# RPI_v5_PCM5122brd.net
KiCad netlist of a schematic drawn in EAGLE
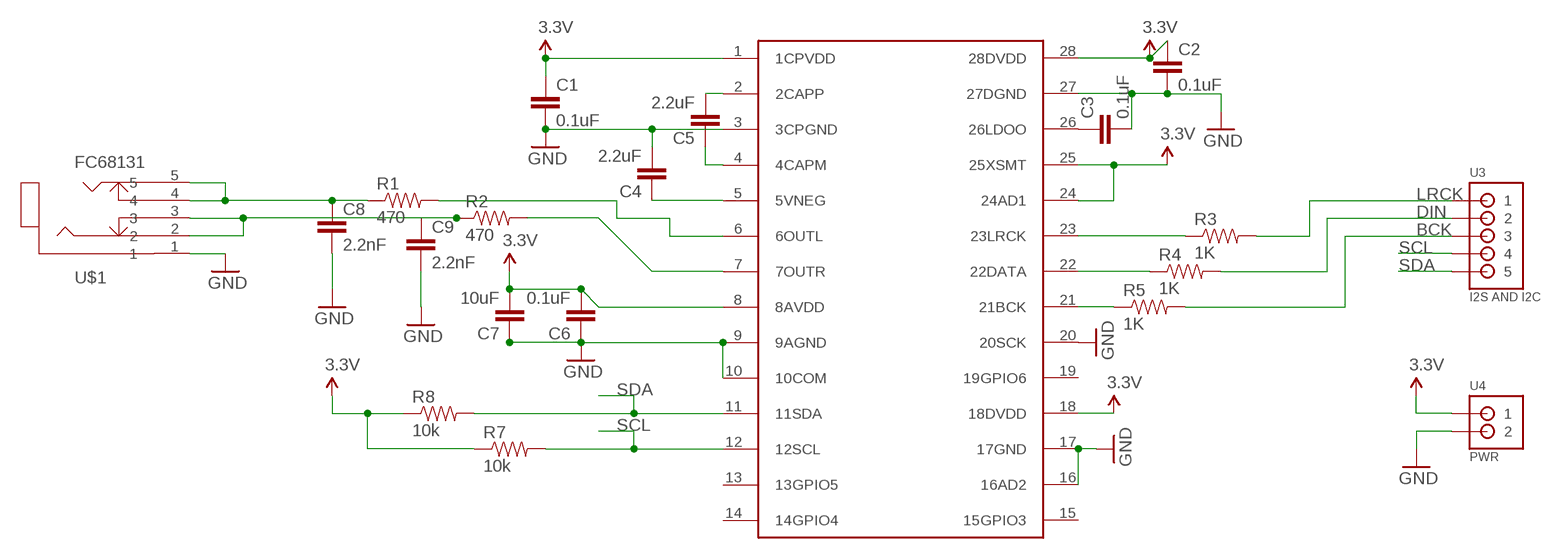
[diagram p0: schematic, sheet 1]

(export (version "E")
  (design (tool "Eeschema 10.0.6"))
  (components
    (comp (ref "C1")
      (value "0.1uF")
      (footprint "eagle-import:0805")
      (libsource (lib "eagle-import") (part "CAP0805"))
    )
    (comp (ref "C2")
      (value "0.1uF")
      (footprint "eagle-import:0805")
      (libsource (lib "eagle-import") (part "CAP0805"))
    )
    (comp (ref "C3")
      (value "0.1uF")
      (footprint "eagle-import:0805")
      (libsource (lib "eagle-import") (part "CAP0805"))
    )
    (comp (ref "C4")
      (value "2.2uF")
      (footprint "eagle-import:0805")
      (libsource (lib "eagle-import") (part "CAP0805"))
    )
    (comp (ref "C5")
      (value "2.2uF")
      (footprint "eagle-import:0805")
      (libsource (lib "eagle-import") (part "CAP0805"))
    )
    (comp (ref "C6")
      (value "0.1uF")
      (footprint "eagle-import:0805")
      (libsource (lib "eagle-import") (part "CAP0805"))
    )
    (comp (ref "C7")
      (value "10uF")
      (footprint "eagle-import:0805")
      (libsource (lib "eagle-import") (part "CAP0805"))
    )
    (comp (ref "C8")
      (value "2.2nF")
      (footprint "eagle-import:CAP-PTH-5MM")
      (libsource (lib "eagle-import") (part "CAPPTH1"))
    )
    (comp (ref "C9")
      (value "2.2nF")
      (footprint "eagle-import:CAP-PTH-5MM")
      (libsource (lib "eagle-import") (part "CAPPTH1"))
    )
    (comp (ref "R1")
      (value "470")
      (footprint "eagle-import:AXIAL-0.4")
      (libsource (lib "eagle-import") (part "RESISTORPTH-1/4W"))
    )
    (comp (ref "R2")
      (value "470")
      (footprint "eagle-import:AXIAL-0.4")
      (libsource (lib "eagle-import") (part "RESISTORPTH-1/4W"))
    )
    (comp (ref "R3")
      (value "1K")
      (footprint "eagle-import:0805")
      (libsource (lib "eagle-import") (part "RESISTOR0805-RES"))
    )
    (comp (ref "R4")
      (value "1K")
      (footprint "eagle-import:0805")
      (libsource (lib "eagle-import") (part "RESISTOR0805-RES"))
    )
    (comp (ref "R5")
      (value "1K")
      (footprint "eagle-import:0805")
      (libsource (lib "eagle-import") (part "RESISTOR0805-RES"))
    )
    (comp (ref "R7")
      (value "10k")
      (footprint "eagle-import:1206")
      (libsource (lib "eagle-import") (part "RESISTOR1206"))
    )
    (comp (ref "R8")
      (value "10k")
      (footprint "eagle-import:1206")
      (libsource (lib "eagle-import") (part "RESISTOR1206"))
    )
    (comp (ref "U$1")
      (value "FC68131")
      (footprint "eagle-import:FC68131-5P")
      (libsource (lib "eagle-import") (part "FC68131"))
    )
    (comp (ref "U$5")
      (value "PCM5122")
      (footprint "eagle-import:TSSOP28")
      (libsource (lib "eagle-import") (part "PCM5122"))
    )
    (comp (ref "U3")
      (value "I2S AND I2C")
      (footprint "eagle-import:JST_B5B-PH_HEADER")
      (libsource (lib "eagle-import") (part "JST-PH_5-PIN_HEADER"))
    )
    (comp (ref "U4")
      (value "PWR")
      (footprint "eagle-import:JST_B2B-PH_HEADER")
      (libsource (lib "eagle-import") (part "JST-PH_2-PIN_HEADER"))
    )
  )
  (nets
    (net (code "1") (name "/BCK") (class "Default")
      (node (ref "R5") (pin "2") (pinfunction "2_2") (pintype "passive"))
      (node (ref "U3") (pin "P3") (pinfunction "3_P3") (pintype "bidirectional"))
    )
    (net (code "2") (name "/DIN") (class "Default")
      (node (ref "R4") (pin "2") (pinfunction "2_2") (pintype "passive"))
      (node (ref "U3") (pin "P2") (pinfunction "2_P2") (pintype "bidirectional"))
    )
    (net (code "3") (name "/LRCK") (class "Default")
      (node (ref "R3") (pin "2") (pinfunction "2_2") (pintype "passive"))
      (node (ref "U3") (pin "P1") (pinfunction "1_P1") (pintype "bidirectional"))
    )
    (net (code "4") (name "/SCL") (class "Default")
      (node (ref "R7") (pin "2") (pinfunction "2_2") (pintype "passive"))
      (node (ref "U$5") (pin "12") (pinfunction "12SCL_12") (pintype "bidirectional"))
      (node (ref "U3") (pin "P4") (pinfunction "4_P4") (pintype "bidirectional"))
    )
    (net (code "5") (name "/SDA") (class "Default")
      (node (ref "R8") (pin "2") (pinfunction "2_2") (pintype "passive"))
      (node (ref "U$5") (pin "11") (pinfunction "11SDA_11") (pintype "bidirectional"))
      (node (ref "U3") (pin "P5") (pinfunction "5_P5") (pintype "bidirectional"))
    )
    (net (code "6") (name "3.3V") (class "Default")
      (node (ref "C1") (pin "1") (pinfunction "1_1") (pintype "passive"))
      (node (ref "C2") (pin "1") (pinfunction "1_1") (pintype "passive"))
      (node (ref "C6") (pin "2") (pinfunction "2_2") (pintype "passive"))
      (node (ref "C7") (pin "2") (pinfunction "2_2") (pintype "passive"))
      (node (ref "R7") (pin "1") (pinfunction "1_1") (pintype "passive"))
      (node (ref "R8") (pin "1") (pinfunction "1_1") (pintype "passive"))
      (node (ref "U$5") (pin "1") (pinfunction "1CPVDD_1") (pintype "bidirectional"))
      (node (ref "U$5") (pin "18") (pinfunction "18DVDD_18") (pintype "bidirectional"))
      (node (ref "U$5") (pin "24") (pinfunction "24AD1_24") (pintype "bidirectional"))
      (node (ref "U$5") (pin "25") (pinfunction "25XSMT_25") (pintype "bidirectional"))
      (node (ref "U$5") (pin "28") (pinfunction "28DVDD_28") (pintype "bidirectional"))
      (node (ref "U$5") (pin "8") (pinfunction "8AVDD_8") (pintype "bidirectional"))
      (node (ref "U4") (pin "P1") (pinfunction "1_P1") (pintype "bidirectional"))
    )
    (net (code "7") (name "GND") (class "Default")
      (node (ref "C1") (pin "2") (pinfunction "2_2") (pintype "passive"))
      (node (ref "C2") (pin "2") (pinfunction "2_2") (pintype "passive"))
      (node (ref "C3") (pin "2") (pinfunction "2_2") (pintype "passive"))
      (node (ref "C4") (pin "2") (pinfunction "2_2") (pintype "passive"))
      (node (ref "C6") (pin "1") (pinfunction "1_1") (pintype "passive"))
      (node (ref "C7") (pin "1") (pinfunction "1_1") (pintype "passive"))
      (node (ref "C8") (pin "2") (pinfunction "2_2") (pintype "passive"))
      (node (ref "C9") (pin "2") (pinfunction "2_2") (pintype "passive"))
      (node (ref "U$1") (pin "1") (pinfunction "1_1") (pintype "bidirectional"))
      (node (ref "U$5") (pin "10") (pinfunction "10COM_10") (pintype "bidirectional"))
      (node (ref "U$5") (pin "16") (pinfunction "16AD2_16") (pintype "bidirectional"))
      (node (ref "U$5") (pin "17") (pinfunction "17GND_17") (pintype "bidirectional"))
      (node (ref "U$5") (pin "20") (pinfunction "20SCK_20") (pintype "bidirectional"))
      (node (ref "U$5") (pin "27") (pinfunction "27DGND_27") (pintype "bidirectional"))
      (node (ref "U$5") (pin "3") (pinfunction "3CPGND_3") (pintype "bidirectional"))
      (node (ref "U$5") (pin "9") (pinfunction "9AGND_9") (pintype "bidirectional"))
      (node (ref "U4") (pin "P2") (pinfunction "2_P2") (pintype "bidirectional"))
    )
    (net (code "8") (name "Net-(R1-1)") (class "Default")
      (node (ref "C8") (pin "1") (pinfunction "1_1") (pintype "passive"))
      (node (ref "R1") (pin "P$1") (pinfunction "1_P$1") (pintype "passive"))
      (node (ref "U$1") (pin "4") (pinfunction "4_4") (pintype "bidirectional"))
      (node (ref "U$1") (pin "5") (pinfunction "5_5") (pintype "bidirectional"))
    )
    (net (code "9") (name "Net-(R1-2)") (class "Default")
      (node (ref "R1") (pin "P$2") (pinfunction "2_P$2") (pintype "passive"))
      (node (ref "U$5") (pin "6") (pinfunction "6OUTL_6") (pintype "bidirectional"))
    )
    (net (code "10") (name "Net-(R2-1)") (class "Default")
      (node (ref "C9") (pin "1") (pinfunction "1_1") (pintype "passive"))
      (node (ref "R2") (pin "P$1") (pinfunction "1_P$1") (pintype "passive"))
      (node (ref "U$1") (pin "2") (pinfunction "2_2") (pintype "bidirectional"))
      (node (ref "U$1") (pin "3") (pinfunction "3_3") (pintype "bidirectional"))
    )
    (net (code "11") (name "Net-(R2-2)") (class "Default")
      (node (ref "R2") (pin "P$2") (pinfunction "2_P$2") (pintype "passive"))
      (node (ref "U$5") (pin "7") (pinfunction "7OUTR_7") (pintype "bidirectional"))
    )
    (net (code "12") (name "Net-(U$5-2CAPP)") (class "Default")
      (node (ref "C5") (pin "2") (pinfunction "2_2") (pintype "passive"))
      (node (ref "U$5") (pin "2") (pinfunction "2CAPP_2") (pintype "bidirectional"))
    )
    (net (code "13") (name "Net-(U$5-4CAPM)") (class "Default")
      (node (ref "C5") (pin "1") (pinfunction "1_1") (pintype "passive"))
      (node (ref "U$5") (pin "4") (pinfunction "4CAPM_4") (pintype "bidirectional"))
    )
    (net (code "14") (name "Net-(U$5-5VNEG)") (class "Default")
      (node (ref "C4") (pin "1") (pinfunction "1_1") (pintype "passive"))
      (node (ref "U$5") (pin "5") (pinfunction "5VNEG_5") (pintype "bidirectional"))
    )
    (net (code "15") (name "Net-(U$5-21BCK)") (class "Default")
      (node (ref "R5") (pin "1") (pinfunction "1_1") (pintype "passive"))
      (node (ref "U$5") (pin "21") (pinfunction "21BCK_21") (pintype "bidirectional"))
    )
    (net (code "16") (name "Net-(U$5-22DATA)") (class "Default")
      (node (ref "R4") (pin "1") (pinfunction "1_1") (pintype "passive"))
      (node (ref "U$5") (pin "22") (pinfunction "22DATA_22") (pintype "bidirectional"))
    )
    (net (code "17") (name "Net-(U$5-23LRCK)") (class "Default")
      (node (ref "R3") (pin "1") (pinfunction "1_1") (pintype "passive"))
      (node (ref "U$5") (pin "23") (pinfunction "23LRCK_23") (pintype "bidirectional"))
    )
    (net (code "18") (name "Net-(U$5-26LDOO)") (class "Default")
      (node (ref "C3") (pin "1") (pinfunction "1_1") (pintype "passive"))
      (node (ref "U$5") (pin "26") (pinfunction "26LDOO_26") (pintype "bidirectional"))
    )
    (net (code "19") (name "unconnected-(U$5-13GPIO5-Pad13)") (class "Default")
      (node (ref "U$5") (pin "13") (pinfunction "13GPIO5_13") (pintype "bidirectional"))
    )
    (net (code "20") (name "unconnected-(U$5-14GPIO4-Pad14)") (class "Default")
      (node (ref "U$5") (pin "14") (pinfunction "14GPIO4_14") (pintype "bidirectional"))
    )
    (net (code "21") (name "unconnected-(U$5-15GPIO3-Pad15)") (class "Default")
      (node (ref "U$5") (pin "15") (pinfunction "15GPIO3_15") (pintype "bidirectional"))
    )
    (net (code "22") (name "unconnected-(U$5-19GPIO6-Pad19)") (class "Default")
      (node (ref "U$5") (pin "19") (pinfunction "19GPIO6_19") (pintype "bidirectional"))
    )
  )
)
